# OpenPack_BATMOD_V1p0_BAT.net
KiCad netlist of a schematic drawn in Altium Designer
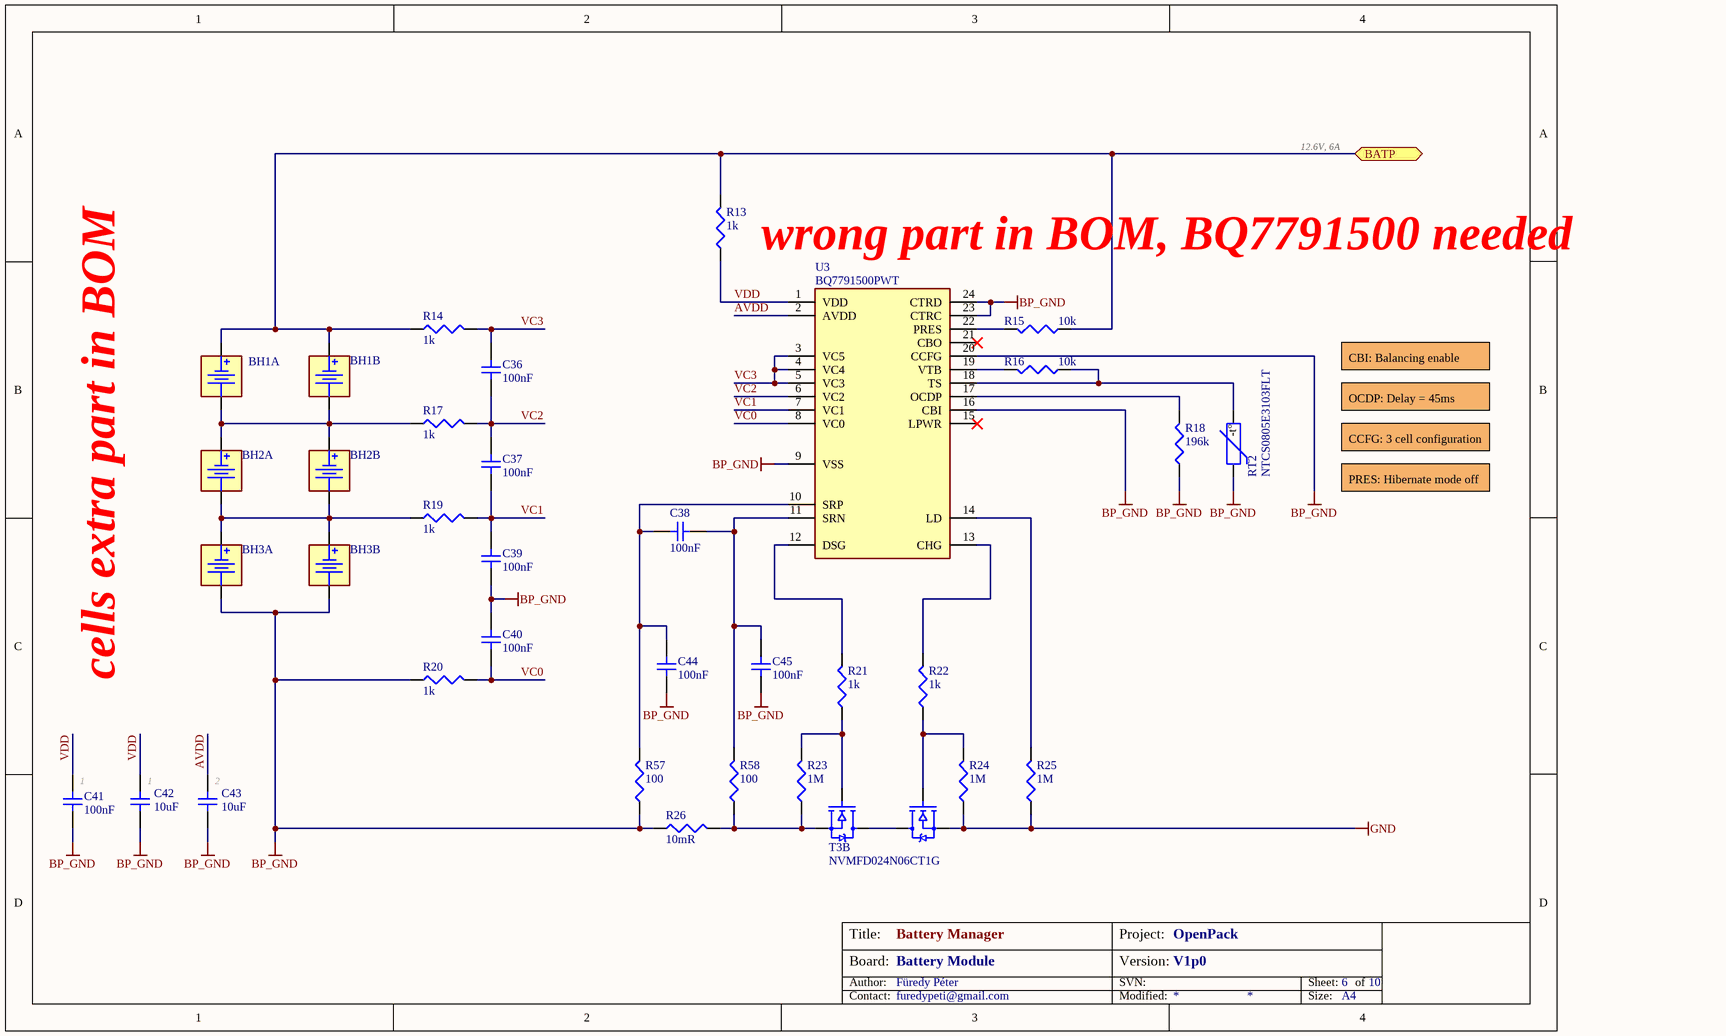
[diagram p0: OpenPack_BATMOD_V1p0_BAT.SchDoc]

(export (version "E")
  (design (tool "Eeschema 10.0.6"))
  (components
    (comp (ref "BH1")
      (value "12BHC186P-GR")
      (footprint "12BHC186P-GR")
      (description "Battery holder, 2x18650")
      (libsource (lib "SCHLIB") (part "12BHC186P-GR"))
    )
    (comp (ref "BH2")
      (value "12BHC186P-GR")
      (footprint "12BHC186P-GR")
      (description "Battery holder, 2x18650")
      (libsource (lib "SCHLIB") (part "12BHC186P-GR"))
    )
    (comp (ref "BH3")
      (value "12BHC186P-GR")
      (footprint "12BHC186P-GR")
      (description "Battery holder, 2x18650")
      (libsource (lib "SCHLIB") (part "12BHC186P-GR"))
    )
    (comp (ref "C36")
      (value "100nF")
      (footprint "CAP_0603")
      (description "MLCC capacitor")
      (libsource (lib "SCHLIB") (part "NP-CAPACITOR"))
    )
    (comp (ref "C37")
      (value "100nF")
      (footprint "CAP_0603")
      (description "MLCC capacitor")
      (libsource (lib "SCHLIB") (part "NP-CAPACITOR"))
    )
    (comp (ref "C38")
      (value "100nF")
      (footprint "CAP_0603")
      (description "MLCC capacitor")
      (libsource (lib "SCHLIB") (part "NP-CAPACITOR"))
    )
    (comp (ref "C39")
      (value "100nF")
      (footprint "CAP_0603")
      (description "MLCC capacitor")
      (libsource (lib "SCHLIB") (part "NP-CAPACITOR"))
    )
    (comp (ref "C40")
      (value "100nF")
      (footprint "CAP_0603")
      (description "MLCC capacitor")
      (libsource (lib "SCHLIB") (part "NP-CAPACITOR"))
    )
    (comp (ref "C41")
      (value "100nF")
      (footprint "CAP_0603")
      (description "MLCC capacitor")
      (libsource (lib "SCHLIB") (part "NP-CAPACITOR"))
    )
    (comp (ref "C42")
      (value "10uF")
      (footprint "CAP_1210")
      (description "UMK325BJ106KM-P")
      (fields (field (name "PART NUMBER") "810-CGA6P1X7R1N106K2"))
      (libsource (lib "SCHLIB") (part "NP-CAPACITOR"))
    )
    (comp (ref "C43")
      (value "10uF")
      (footprint "CAP_1210")
      (description "UMK325BJ106KM-P")
      (fields (field (name "PART NUMBER") "810-CGA6P1X7R1N106K2"))
      (libsource (lib "SCHLIB") (part "NP-CAPACITOR"))
    )
    (comp (ref "C44")
      (value "100nF")
      (footprint "CAP_0603")
      (description "MLCC capacitor")
      (libsource (lib "SCHLIB") (part "NP-CAPACITOR"))
    )
    (comp (ref "C45")
      (value "100nF")
      (footprint "CAP_0603")
      (description "MLCC capacitor")
      (libsource (lib "SCHLIB") (part "NP-CAPACITOR"))
    )
    (comp (ref "R13")
      (value "1k")
      (footprint "RES-0603")
      (description "Metal Film Resistor")
      (libsource (lib "SCHLIB") (part "RESISTOR"))
    )
    (comp (ref "R14")
      (value "1k")
      (footprint "RES-0603")
      (description "Metal Film Resistor")
      (libsource (lib "SCHLIB") (part "RESISTOR"))
    )
    (comp (ref "R15")
      (value "10k")
      (footprint "RES-0603")
      (description "Metal Film Resistor")
      (libsource (lib "SCHLIB") (part "RESISTOR"))
    )
    (comp (ref "R16")
      (value "10k")
      (footprint "RES-0603")
      (description "Metal Film Resistor")
      (libsource (lib "SCHLIB") (part "RESISTOR"))
    )
    (comp (ref "R17")
      (value "1k")
      (footprint "RES-0603")
      (description "Metal Film Resistor")
      (libsource (lib "SCHLIB") (part "RESISTOR"))
    )
    (comp (ref "R18")
      (value "196k")
      (footprint "RES-0603")
      (description "Metal Film Resistor")
      (libsource (lib "SCHLIB") (part "RESISTOR"))
    )
    (comp (ref "R19")
      (value "1k")
      (footprint "RES-0603")
      (description "Metal Film Resistor")
      (libsource (lib "SCHLIB") (part "RESISTOR"))
    )
    (comp (ref "R20")
      (value "1k")
      (footprint "RES-0603")
      (description "Metal Film Resistor")
      (libsource (lib "SCHLIB") (part "RESISTOR"))
    )
    (comp (ref "R21")
      (value "1k")
      (footprint "RES-0603")
      (description "Metal Film Resistor")
      (libsource (lib "SCHLIB") (part "RESISTOR"))
    )
    (comp (ref "R22")
      (value "1k")
      (footprint "RES-0603")
      (description "Metal Film Resistor")
      (libsource (lib "SCHLIB") (part "RESISTOR"))
    )
    (comp (ref "R23")
      (value "1M")
      (footprint "RES-0603")
      (description "Metal Film Resistor")
      (libsource (lib "SCHLIB") (part "RESISTOR"))
    )
    (comp (ref "R24")
      (value "1M")
      (footprint "RES-0603")
      (description "Metal Film Resistor")
      (libsource (lib "SCHLIB") (part "RESISTOR"))
    )
    (comp (ref "R25")
      (value "1M")
      (footprint "RES-0603")
      (description "Metal Film Resistor")
      (libsource (lib "SCHLIB") (part "RESISTOR"))
    )
    (comp (ref "R26")
      (value "10mR")
      (footprint "RES-2512")
      (description "Metal Film Resistor")
      (libsource (lib "SCHLIB") (part "RESISTOR"))
    )
    (comp (ref "R57")
      (value "100")
      (footprint "RES-0603")
      (description "Metal Film Resistor")
      (libsource (lib "SCHLIB") (part "RESISTOR"))
    )
    (comp (ref "R58")
      (value "100")
      (footprint "RES-0603")
      (description "Metal Film Resistor")
      (libsource (lib "SCHLIB") (part "RESISTOR"))
    )
    (comp (ref "RT2")
      (value "NTCS0805E3103FLT")
      (footprint "RES-0805")
      (description "NTC (Negative Temperature Coefficient) Thermistors 10Kohms 1%")
      (fields (field (name "PART NUMBER") "594-NTCS0805E3103FLT"))
      (libsource (lib "SCHLIB") (part "NTCS0805E3103FLT"))
    )
    (comp (ref "T3")
      (value "NVMFD024N06CT1G")
      (footprint "SO-8FL (DFN8)")
      (description "Power NMOSFET Dual, 60V, 24A, 22mΩ")
      (fields (field (name "PART NUMBER") "863-NVMFD024N06CT1G"))
      (libsource (lib "SCHLIB") (part "NVMFD024N06CT1G"))
    )
    (comp (ref "U3")
      (value "BQ7791500PWT")
      (footprint "TSSOP24")
      (description "Battery Management 3-series to 5-series stackable")
      (fields (field (name "PART NUMBER") "595-BQ7791506PWR"))
      (libsource (lib "SCHLIB") (part "BQ7791500PWT"))
    )
  )
  (nets
    (net (code "1") (name "/AVDD") (class "Default")
      (node (ref "C43") (pin "2") (pinfunction "2_2") (pintype "passive"))
      (node (ref "U3") (pin "2") (pinfunction "AVDD_2") (pintype "passive"))
    )
    (net (code "2") (name "/BATP") (class "Default")
      (node (ref "BH1") (pin "2") (pinfunction "2_2") (pintype "passive"))
      (node (ref "BH1") (pin "4") (pinfunction "4_4") (pintype "passive"))
      (node (ref "R13") (pin "2") (pintype "passive"))
      (node (ref "R14") (pin "1") (pintype "passive"))
      (node (ref "R15") (pin "1") (pintype "passive"))
    )
    (net (code "3") (name "/VC0") (class "Default")
      (node (ref "C40") (pin "1") (pinfunction "1_1") (pintype "passive"))
      (node (ref "R20") (pin "2") (pintype "passive"))
      (node (ref "U3") (pin "8") (pinfunction "VC0_8") (pintype "passive"))
    )
    (net (code "4") (name "/VC1") (class "Default")
      (node (ref "C37") (pin "1") (pinfunction "1_1") (pintype "passive"))
      (node (ref "C39") (pin "2") (pinfunction "2_2") (pintype "passive"))
      (node (ref "R19") (pin "2") (pintype "passive"))
      (node (ref "U3") (pin "7") (pinfunction "VC1_7") (pintype "passive"))
    )
    (net (code "5") (name "/VC2") (class "Default")
      (node (ref "C36") (pin "1") (pinfunction "1_1") (pintype "passive"))
      (node (ref "C37") (pin "2") (pinfunction "2_2") (pintype "passive"))
      (node (ref "R17") (pin "2") (pintype "passive"))
      (node (ref "U3") (pin "6") (pinfunction "VC2_6") (pintype "passive"))
    )
    (net (code "6") (name "/VC3") (class "Default")
      (node (ref "C36") (pin "2") (pinfunction "2_2") (pintype "passive"))
      (node (ref "R14") (pin "2") (pintype "passive"))
      (node (ref "U3") (pin "3") (pinfunction "VC5_3") (pintype "passive"))
      (node (ref "U3") (pin "4") (pinfunction "VC4_4") (pintype "passive"))
      (node (ref "U3") (pin "5") (pinfunction "VC3_5") (pintype "passive"))
    )
    (net (code "7") (name "/VDD") (class "Default")
      (node (ref "C41") (pin "2") (pinfunction "2_2") (pintype "passive"))
      (node (ref "C42") (pin "2") (pinfunction "2_2") (pintype "passive"))
      (node (ref "R13") (pin "1") (pintype "passive"))
      (node (ref "U3") (pin "1") (pinfunction "VDD_1") (pintype "passive"))
    )
    (net (code "8") (name "BP_GND") (class "Default")
      (node (ref "BH3") (pin "1") (pinfunction "1_1") (pintype "passive"))
      (node (ref "BH3") (pin "3") (pinfunction "3_3") (pintype "passive"))
      (node (ref "C39") (pin "1") (pinfunction "1_1") (pintype "passive"))
      (node (ref "C40") (pin "2") (pinfunction "2_2") (pintype "passive"))
      (node (ref "C41") (pin "1") (pinfunction "1_1") (pintype "passive"))
      (node (ref "C42") (pin "1") (pinfunction "1_1") (pintype "passive"))
      (node (ref "C43") (pin "1") (pinfunction "1_1") (pintype "passive"))
      (node (ref "C44") (pin "1") (pinfunction "1_1") (pintype "passive"))
      (node (ref "C45") (pin "1") (pinfunction "1_1") (pintype "passive"))
      (node (ref "R18") (pin "1") (pintype "passive"))
      (node (ref "R20") (pin "1") (pintype "passive"))
      (node (ref "R26") (pin "1") (pintype "passive"))
      (node (ref "R57") (pin "1") (pintype "passive"))
      (node (ref "RT2") (pin "1") (pintype "passive"))
      (node (ref "U3") (pin "16") (pinfunction "CBI_16") (pintype "passive"))
      (node (ref "U3") (pin "20") (pinfunction "CCFG_20") (pintype "passive"))
      (node (ref "U3") (pin "23") (pinfunction "CTRC_23") (pintype "passive"))
      (node (ref "U3") (pin "24") (pinfunction "CTRD_24") (pintype "passive"))
      (node (ref "U3") (pin "9") (pinfunction "VSS_9") (pintype "passive"))
    )
    (net (code "9") (name "GND") (class "Default")
      (node (ref "R24") (pin "1") (pintype "passive"))
      (node (ref "R25") (pin "1") (pintype "passive"))
      (node (ref "T3") (pin "3") (pinfunction "3_3") (pintype "passive"))
    )
    (net (code "10") (name "Net-(BH1-Pad1)") (class "Default")
      (node (ref "BH1") (pin "1") (pinfunction "1_1") (pintype "passive"))
      (node (ref "BH1") (pin "3") (pinfunction "3_3") (pintype "passive"))
      (node (ref "BH2") (pin "2") (pinfunction "2_2") (pintype "passive"))
      (node (ref "BH2") (pin "4") (pinfunction "4_4") (pintype "passive"))
      (node (ref "R17") (pin "1") (pintype "passive"))
    )
    (net (code "11") (name "Net-(BH2-Pad1)") (class "Default")
      (node (ref "BH2") (pin "1") (pinfunction "1_1") (pintype "passive"))
      (node (ref "BH2") (pin "3") (pinfunction "3_3") (pintype "passive"))
      (node (ref "BH3") (pin "2") (pinfunction "2_2") (pintype "passive"))
      (node (ref "BH3") (pin "4") (pinfunction "4_4") (pintype "passive"))
      (node (ref "R19") (pin "1") (pintype "passive"))
    )
    (net (code "12") (name "Net-(R21-Pad1)") (class "Default")
      (node (ref "R21") (pin "1") (pintype "passive"))
      (node (ref "R23") (pin "2") (pintype "passive"))
      (node (ref "T3") (pin "2") (pinfunction "2_2") (pintype "passive"))
    )
    (net (code "13") (name "Net-(R22-Pad1)") (class "Default")
      (node (ref "R22") (pin "1") (pintype "passive"))
      (node (ref "R24") (pin "2") (pintype "passive"))
      (node (ref "T3") (pin "4") (pinfunction "4_4") (pintype "passive"))
    )
    (net (code "14") (name "Net-(R23-Pad1)") (class "Default")
      (node (ref "R23") (pin "1") (pintype "passive"))
      (node (ref "R26") (pin "2") (pintype "passive"))
      (node (ref "R58") (pin "1") (pintype "passive"))
      (node (ref "T3") (pin "1") (pinfunction "1_1") (pintype "passive"))
    )
    (net (code "15") (name "Net-(T3-Pad10)") (class "Default")
      (node (ref "T3") (pin "10") (pinfunction "10_10") (pintype "passive"))
      (node (ref "T3") (pin "9") (pinfunction "9_9") (pintype "passive"))
    )
    (net (code "16") (name "Net-(U3-CHG)") (class "Default")
      (node (ref "R22") (pin "2") (pintype "passive"))
      (node (ref "U3") (pin "13") (pinfunction "CHG_13") (pintype "passive"))
    )
    (net (code "17") (name "Net-(U3-DSG)") (class "Default")
      (node (ref "R21") (pin "2") (pintype "passive"))
      (node (ref "U3") (pin "12") (pinfunction "DSG_12") (pintype "passive"))
    )
    (net (code "18") (name "Net-(U3-LD)") (class "Default")
      (node (ref "R25") (pin "2") (pintype "passive"))
      (node (ref "U3") (pin "14") (pinfunction "LD_14") (pintype "passive"))
    )
    (net (code "19") (name "Net-(U3-OCDP)") (class "Default")
      (node (ref "R18") (pin "2") (pintype "passive"))
      (node (ref "U3") (pin "17") (pinfunction "OCDP_17") (pintype "passive"))
    )
    (net (code "20") (name "Net-(U3-PRES)") (class "Default")
      (node (ref "R15") (pin "2") (pintype "passive"))
      (node (ref "U3") (pin "22") (pinfunction "PRES_22") (pintype "passive"))
    )
    (net (code "21") (name "Net-(U3-SRN)") (class "Default")
      (node (ref "C38") (pin "1") (pinfunction "1_1") (pintype "passive"))
      (node (ref "C45") (pin "2") (pinfunction "2_2") (pintype "passive"))
      (node (ref "R58") (pin "2") (pintype "passive"))
      (node (ref "U3") (pin "11") (pinfunction "SRN_11") (pintype "passive"))
    )
    (net (code "22") (name "Net-(U3-SRP)") (class "Default")
      (node (ref "C38") (pin "2") (pinfunction "2_2") (pintype "passive"))
      (node (ref "C44") (pin "2") (pinfunction "2_2") (pintype "passive"))
      (node (ref "R57") (pin "2") (pintype "passive"))
      (node (ref "U3") (pin "10") (pinfunction "SRP_10") (pintype "passive"))
    )
    (net (code "23") (name "Net-(U3-TS)") (class "Default")
      (node (ref "R16") (pin "1") (pintype "passive"))
      (node (ref "RT2") (pin "2") (pintype "passive"))
      (node (ref "U3") (pin "18") (pinfunction "TS_18") (pintype "passive"))
    )
    (net (code "24") (name "Net-(U3-VTB)") (class "Default")
      (node (ref "R16") (pin "2") (pintype "passive"))
      (node (ref "U3") (pin "19") (pinfunction "VTB_19") (pintype "passive"))
    )
    (net (code "25") (name "unconnected-(U3-CBO-Pad21)") (class "Default")
      (node (ref "U3") (pin "21") (pinfunction "CBO_21") (pintype "passive+no_connect"))
    )
    (net (code "26") (name "unconnected-(U3-LPWR-Pad15)") (class "Default")
      (node (ref "U3") (pin "15") (pinfunction "LPWR_15") (pintype "passive+no_connect"))
    )
  )
)
